# RANGKAIAN_SISTEM_KESELURUHAN.net
KiCad netlist of a schematic drawn in EasyEDA
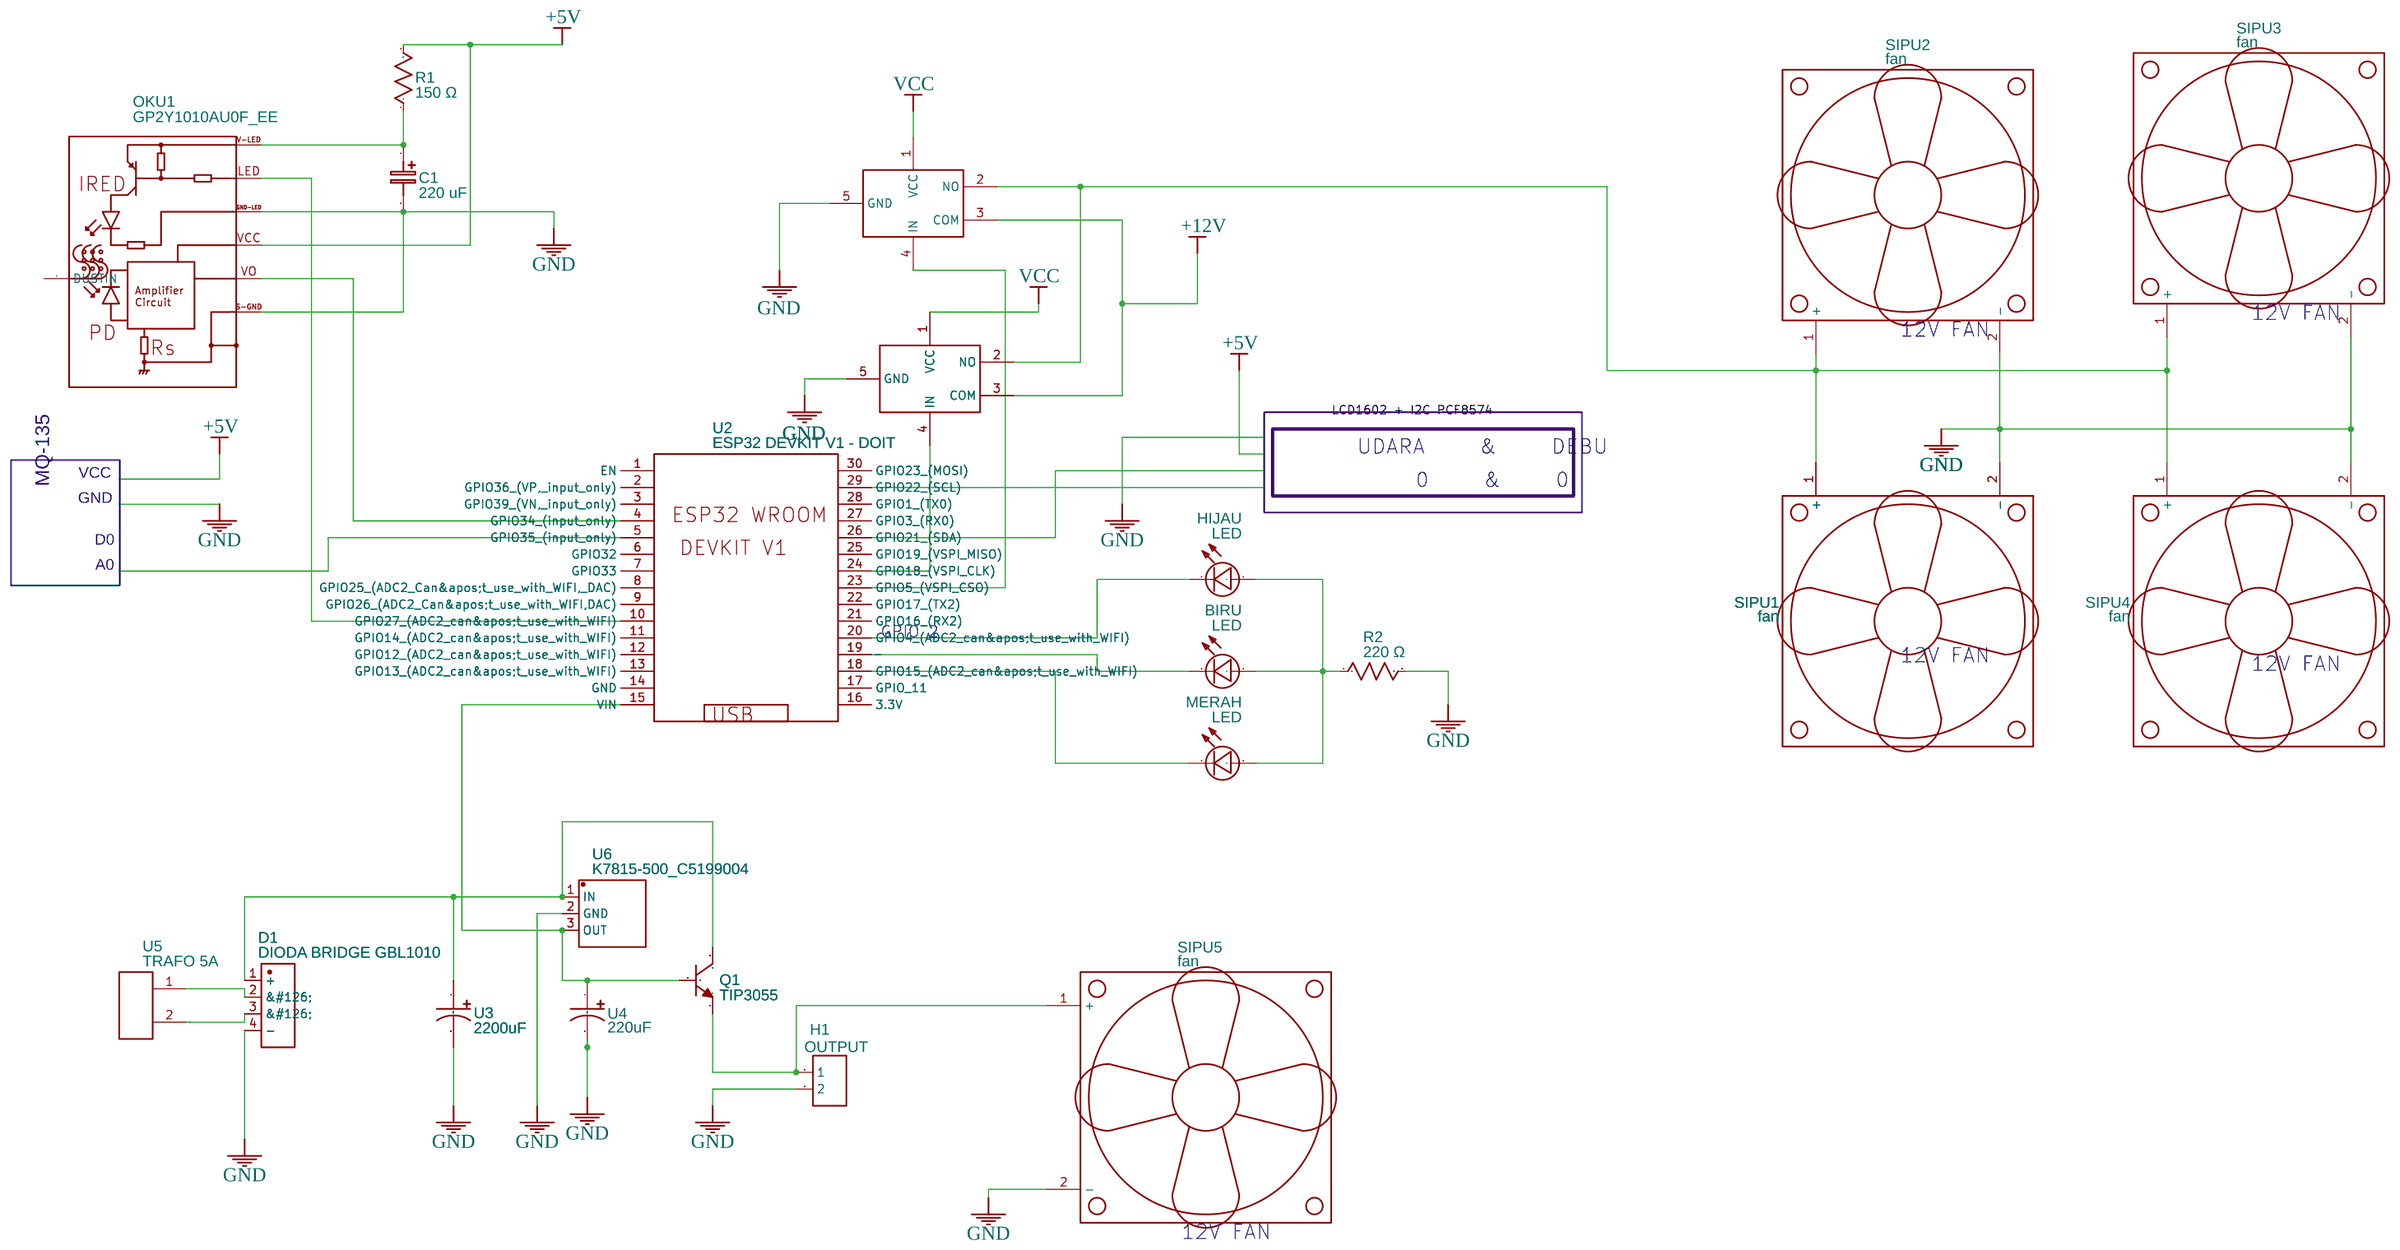
[diagram p0: schematic sheet]

(export (version "E")
  (design (tool "Eeschema 10.0.6"))
  (components
    (comp (ref "BIRU") (value "LED") (libsource (lib "") (part "LED_2")))
    (comp (ref "C1") (value "220 uF") (libsource (lib "") (part "C_Tan_SMD_A_EU")))
    (comp (ref "D1")
      (value "DIODA BRIDGE GBL1010")
      (fields (field (name "BOM_Manufacturer Part") "GBU1010") (field (name "BOM_Supplier Part") "C525760"))
      (libsource (lib "") (part "Dioda Bridge 10A"))
    )
    (comp (ref "H1")
      (value "OUTPUT")
      (fields (field (name "BOM_Supplier Part") "C49661"))
      (libsource (lib "") (part "HDR-F-2.54_1x2"))
    )
    (comp (ref "HIJAU") (value "LED") (libsource (lib "") (part "LED")))
    (comp (ref "MERAH") (value "LED") (libsource (lib "") (part "LED_1")))
    (comp (ref "OKU1")
      (value "GP2Y1010AU0F_EE")
      (fields (field (name "BOM_Manufacturer Part") "?"))
      (libsource (lib "") (part "GP2Y1010AU0F_EE_IN DEVELOPMENT"))
    )
    (comp (ref "Q1")
      (value "TIP3055")
      (fields
        (field (name "BOM_Manufacturer Part") "2n3904S-RTK/PS")
        (field (name "BOM_Supplier Part") "C18536")
      )
      (libsource (lib "") (part "2N3904(SOT-23)"))
    )
    (comp (ref "R1") (value "150 Ω") (libsource (lib "") (part "R_0603_US_1")))
    (comp (ref "R2") (value "220 Ω") (libsource (lib "") (part "R_0603_US")))
    (comp (ref "SIPU1")
      (value "fan")
      (fields (field (name "BOM_Manufacturer Part") "?"))
      (libsource (lib "") (part "Unknown_1165_-415"))
    )
    (comp (ref "SIPU2")
      (value "fan")
      (fields (field (name "BOM_Manufacturer Part") "?"))
      (libsource (lib "") (part "Unknown_1165_-660"))
    )
    (comp (ref "SIPU3")
      (value "fan")
      (fields (field (name "BOM_Manufacturer Part") "?"))
      (libsource (lib "") (part "Unknown_1375_-670"))
    )
    (comp (ref "SIPU4")
      (value "fan")
      (fields (field (name "BOM_Manufacturer Part") "?"))
      (libsource (lib "") (part "Unknown_1375_-415"))
    )
    (comp (ref "SIPU5")
      (value "fan")
      (fields (field (name "BOM_Manufacturer Part") "?"))
      (libsource (lib "") (part "Unknown_735_-120"))
    )
    (comp (ref "U1") (value "Relay 5P") (libsource (lib "") (part "Relay 5P")))
    (comp (ref "U2") (value "ESP32 DEVKIT V1 - DOIT") (libsource (lib "") (part "ESP32 DEVKIT V1 - DOIT")))
    (comp (ref "U3") (value "2200uF") (libsource (lib "") (part "kapasitor")))
    (comp (ref "U4") (value "220uF") (libsource (lib "") (part "kapasitor")))
    (comp (ref "U5") (value "TRAFO 5A") (libsource (lib "") (part "Kapasitor_yatik")))
    (comp (ref "U6")
      (value "K7815-500_C5199004")
      (fields
        (field (name "BOM_Manufacturer Part") "K7809-500")
        (field (name "BOM_Supplier Part") "C5199004")
      )
      (libsource (lib "") (part "K7809-500_C5199004"))
    )
    (comp (ref "U7") (value "Relay 5P") (libsource (lib "") (part "Relay 5P")))
  )
  (nets
    (net (code "1") (name "+5V") (class "Default")
      (node (ref "OKU1") (pin "VCC") (pinfunction "VCC_VCC") (pintype "input"))
      (node (ref "R1") (pin "2") (pinfunction "2_2") (pintype "unspecified"))
    )
    (net (code "2") (name "+12V") (class "Default")
      (node (ref "U1") (pin "3") (pinfunction "COM_3") (pintype "output"))
      (node (ref "U7") (pin "3") (pinfunction "COM_3") (pintype "output"))
    )
    (net (code "4") (name "GND") (class "Default")
      (node (ref "C1") (pin "2") (pinfunction "2_2") (pintype "unspecified"))
      (node (ref "D1") (pin "4") (pinfunction "-_4") (pintype "unspecified"))
      (node (ref "H1") (pin "2") (pinfunction "2_2") (pintype "input"))
      (node (ref "OKU1") (pin "GND-LED") (pinfunction "LEDGND_GND-LED") (pintype "input"))
      (node (ref "OKU1") (pin "S-GND") (pinfunction "SGND_S-GND") (pintype "input"))
      (node (ref "R2") (pin "2") (pinfunction "2_2") (pintype "unspecified"))
      (node (ref "SIPU1") (pin "2") (pinfunction "-_2") (pintype "unspecified"))
      (node (ref "SIPU2") (pin "2") (pinfunction "-_2") (pintype "unspecified"))
      (node (ref "SIPU3") (pin "2") (pinfunction "-_2") (pintype "unspecified"))
      (node (ref "SIPU4") (pin "2") (pinfunction "-_2") (pintype "unspecified"))
      (node (ref "SIPU5") (pin "2") (pinfunction "-_2") (pintype "unspecified"))
      (node (ref "U1") (pin "5") (pinfunction "GND_5") (pintype "input"))
      (node (ref "U3") (pin "2") (pinfunction "2_2") (pintype "unspecified"))
      (node (ref "U4") (pin "2") (pinfunction "2_2") (pintype "unspecified"))
      (node (ref "U6") (pin "2") (pinfunction "GND_2") (pintype "unspecified"))
      (node (ref "U7") (pin "5") (pinfunction "GND_5") (pintype "input"))
    )
    (net (code "5") (name "Net-(BIRU-+)") (class "Default")
      (node (ref "BIRU") (pin "1") (pinfunction "+_1") (pintype "unspecified"))
      (node (ref "HIJAU") (pin "1") (pinfunction "+_1") (pintype "unspecified"))
      (node (ref "MERAH") (pin "1") (pinfunction "+_1") (pintype "unspecified"))
      (node (ref "R2") (pin "1") (pinfunction "1_1") (pintype "unspecified"))
    )
    (net (code "6") (name "Net-(BIRU--)") (class "Default")
      (node (ref "BIRU") (pin "2") (pinfunction "-_2") (pintype "unspecified"))
      (node (ref "U2") (pin "19") (pinfunction "GPIO2_(ADC2_can&apos;t_use_with_WIFI)_19") (pintype "unspecified"))
    )
    (net (code "7") (name "Net-(D1-+)") (class "Default")
      (node (ref "D1") (pin "1") (pinfunction "+_1") (pintype "unspecified"))
      (node (ref "Q1") (pin "3") (pinfunction "C_3") (pintype "input"))
      (node (ref "U3") (pin "1") (pinfunction "1_1") (pintype "unspecified"))
      (node (ref "U6") (pin "1") (pinfunction "IN_1") (pintype "unspecified"))
    )
    (net (code "8") (name "Net-(HIJAU--)") (class "Default")
      (node (ref "HIJAU") (pin "2") (pinfunction "-_2") (pintype "unspecified"))
      (node (ref "U2") (pin "20") (pinfunction "GPIO4_(ADC2_can&apos;t_use_with_WIFI)_20") (pintype "unspecified"))
    )
    (net (code "9") (name "Net-(MERAH--)") (class "Default")
      (node (ref "MERAH") (pin "2") (pinfunction "-_2") (pintype "unspecified"))
      (node (ref "U2") (pin "18") (pinfunction "GPIO15_(ADC2_can&apos;t_use_with_WIFI)_18") (pintype "unspecified"))
    )
    (net (code "10") (name "Net-(OKU1-VLED)") (class "Default")
      (node (ref "C1") (pin "1") (pinfunction "1_1") (pintype "unspecified"))
      (node (ref "OKU1") (pin "V-LED") (pinfunction "VLED_V-LED") (pintype "input"))
      (node (ref "R1") (pin "1") (pinfunction "1_1") (pintype "unspecified"))
    )
    (net (code "11") (name "Net-(Q1-B)") (class "Default")
      (node (ref "Q1") (pin "2") (pinfunction "B_2") (pintype "input"))
      (node (ref "U2") (pin "15") (pinfunction "VIN_15") (pintype "unspecified"))
      (node (ref "U4") (pin "1") (pinfunction "1_1") (pintype "unspecified"))
      (node (ref "U6") (pin "3") (pinfunction "OUT_3") (pintype "unspecified"))
    )
    (net (code "12") (name "Net-(Q1-E)") (class "Default")
      (node (ref "H1") (pin "1") (pinfunction "1_1") (pintype "input"))
      (node (ref "Q1") (pin "1") (pinfunction "E_1") (pintype "input"))
      (node (ref "SIPU5") (pin "1") (pinfunction "+_1") (pintype "unspecified"))
    )
    (net (code "13") (name "Net-(SIPU1-+)") (class "Default")
      (node (ref "SIPU1") (pin "1") (pinfunction "+_1") (pintype "unspecified"))
      (node (ref "SIPU2") (pin "1") (pinfunction "+_1") (pintype "unspecified"))
      (node (ref "SIPU3") (pin "1") (pinfunction "+_1") (pintype "unspecified"))
      (node (ref "SIPU4") (pin "1") (pinfunction "+_1") (pintype "unspecified"))
      (node (ref "U1") (pin "2") (pinfunction "NO_2") (pintype "output"))
      (node (ref "U7") (pin "2") (pinfunction "NO_2") (pintype "output"))
    )
    (net (code "14") (name "Net-(U1-IN)") (class "Default")
      (node (ref "U1") (pin "4") (pinfunction "IN_4") (pintype "bidirectional"))
      (node (ref "U2") (pin "24") (pinfunction "GPIO18_(VSPI_CLK)_24") (pintype "unspecified"))
    )
    (net (code "15") (name "Net-(U2-GPIO5_(VSPI_CSO))") (class "Default")
      (node (ref "U2") (pin "23") (pinfunction "GPIO5_(VSPI_CSO)_23") (pintype "unspecified"))
      (node (ref "U7") (pin "4") (pinfunction "IN_4") (pintype "bidirectional"))
    )
    (net (code "16") (name "Net-(U2-GPIO27_(ADC2_can&apos;t_use_with_WIFI))") (class "Default")
      (node (ref "OKU1") (pin "LED") (pinfunction "LED_LED") (pintype "input"))
      (node (ref "U2") (pin "10") (pinfunction "GPIO27_(ADC2_can&apos;t_use_with_WIFI)_10") (pintype "unspecified"))
    )
    (net (code "17") (name "Net-(U2-GPIO34_(input_only))") (class "Default")
      (node (ref "OKU1") (pin "VO") (pinfunction "VO_VO") (pintype "input"))
      (node (ref "U2") (pin "4") (pinfunction "GPIO34_(input_only)_4") (pintype "unspecified"))
    )
    (net (code "18") (name "VCC") (class "Default")
      (node (ref "U1") (pin "1") (pinfunction "VCC_1") (pintype "bidirectional"))
      (node (ref "U7") (pin "1") (pinfunction "VCC_1") (pintype "bidirectional"))
    )
    (net (code "19") (name "unconnected-(D1-&#126;-Pad2)") (class "Default")
      (node (ref "D1") (pin "2") (pinfunction "&#126;_2") (pintype "unspecified"))
    )
    (net (code "20") (name "unconnected-(D1-&#126;-Pad3)") (class "Default")
      (node (ref "D1") (pin "3") (pinfunction "&#126;_3") (pintype "unspecified"))
    )
    (net (code "21") (name "unconnected-(OKU1-DUSTIN-Pad7)") (class "Default")
      (node (ref "OKU1") (pin "7") (pinfunction "DUSTIN_7") (pintype "unspecified"))
    )
    (net (code "22") (name "unconnected-(U2-3.3V-Pad16)") (class "Default")
      (node (ref "U2") (pin "16") (pinfunction "3.3V_16") (pintype "unspecified"))
    )
    (net (code "23") (name "unconnected-(U2-EN-Pad1)") (class "Default")
      (node (ref "U2") (pin "1") (pinfunction "EN_1") (pintype "unspecified"))
    )
    (net (code "24") (name "unconnected-(U2-GND-Pad14)") (class "Default")
      (node (ref "U2") (pin "14") (pinfunction "GND_14") (pintype "unspecified"))
    )
    (net (code "25") (name "unconnected-(U2-GPIO1_(TX0)-Pad28)") (class "Default")
      (node (ref "U2") (pin "28") (pinfunction "GPIO1_(TX0)_28") (pintype "unspecified"))
    )
    (net (code "26") (name "unconnected-(U2-GPIO3_(RX0)-Pad27)") (class "Default")
      (node (ref "U2") (pin "27") (pinfunction "GPIO3_(RX0)_27") (pintype "unspecified"))
    )
    (net (code "27") (name "unconnected-(U2-GPIO12_(ADC2_can&apos;t_use_with_WIFI)-Pad12)") (class "Default")
      (node (ref "U2") (pin "12") (pinfunction "GPIO12_(ADC2_can&apos;t_use_with_WIFI)_12") (pintype "unspecified"))
    )
    (net (code "28") (name "unconnected-(U2-GPIO13_(ADC2_can&apos;t_use_with_WIFI)-Pad13)") (class "Default")
      (node (ref "U2") (pin "13") (pinfunction "GPIO13_(ADC2_can&apos;t_use_with_WIFI)_13") (pintype "unspecified"))
    )
    (net (code "29") (name "unconnected-(U2-GPIO14_(ADC2_can&apos;t_use_with_WIFI)-Pad11)") (class "Default")
      (node (ref "U2") (pin "11") (pinfunction "GPIO14_(ADC2_can&apos;t_use_with_WIFI)_11") (pintype "unspecified"))
    )
    (net (code "30") (name "unconnected-(U2-GPIO16_(RX2)-Pad21)") (class "Default")
      (node (ref "U2") (pin "21") (pinfunction "GPIO16_(RX2)_21") (pintype "unspecified"))
    )
    (net (code "31") (name "unconnected-(U2-GPIO17_(TX2)-Pad22)") (class "Default")
      (node (ref "U2") (pin "22") (pinfunction "GPIO17_(TX2)_22") (pintype "unspecified"))
    )
    (net (code "32") (name "unconnected-(U2-GPIO19_(VSPI_MISO)-Pad25)") (class "Default")
      (node (ref "U2") (pin "25") (pinfunction "GPIO19_(VSPI_MISO)_25") (pintype "unspecified"))
    )
    (net (code "33") (name "unconnected-(U2-GPIO21_(SDA)-Pad26)") (class "Default")
      (node (ref "U2") (pin "26") (pinfunction "GPIO21_(SDA)_26") (pintype "unspecified"))
    )
    (net (code "34") (name "unconnected-(U2-GPIO22_(SCL)-Pad29)") (class "Default")
      (node (ref "U2") (pin "29") (pinfunction "GPIO22_(SCL)_29") (pintype "unspecified"))
    )
    (net (code "35") (name "unconnected-(U2-GPIO23_(MOSI)-Pad30)") (class "Default")
      (node (ref "U2") (pin "30") (pinfunction "GPIO23_(MOSI)_30") (pintype "unspecified"))
    )
    (net (code "36") (name "unconnected-(U2-GPIO25_(ADC2_Can&apos;t_use_with_WIFI,_DAC)-Pad8)") (class "Default")
      (node (ref "U2") (pin "8") (pinfunction "GPIO25_(ADC2_Can&apos;t_use_with_WIFI,_DAC)_8") (pintype "unspecified"))
    )
    (net (code "37") (name "unconnected-(U2-GPIO26_(ADC2_Can&apos;t_use_with_WIFI,DAC)-Pad9)") (class "Default")
      (node (ref "U2") (pin "9") (pinfunction "GPIO26_(ADC2_Can&apos;t_use_with_WIFI,DAC)_9") (pintype "unspecified"))
    )
    (net (code "38") (name "unconnected-(U2-GPIO32-Pad6)") (class "Default")
      (node (ref "U2") (pin "6") (pinfunction "GPIO32_6") (pintype "unspecified"))
    )
    (net (code "39") (name "unconnected-(U2-GPIO33-Pad7)") (class "Default")
      (node (ref "U2") (pin "7") (pinfunction "GPIO33_7") (pintype "unspecified"))
    )
    (net (code "40") (name "unconnected-(U2-GPIO35_(input_only)-Pad5)") (class "Default")
      (node (ref "U2") (pin "5") (pinfunction "GPIO35_(input_only)_5") (pintype "unspecified"))
    )
    (net (code "41") (name "unconnected-(U2-GPIO36_(VP,_input_only)-Pad2)") (class "Default")
      (node (ref "U2") (pin "2") (pinfunction "GPIO36_(VP,_input_only)_2") (pintype "unspecified"))
    )
    (net (code "42") (name "unconnected-(U2-GPIO39_(VN,_input_only)-Pad3)") (class "Default")
      (node (ref "U2") (pin "3") (pinfunction "GPIO39_(VN,_input_only)_3") (pintype "unspecified"))
    )
    (net (code "43") (name "unconnected-(U2-GPIO_11-Pad17)") (class "Default")
      (node (ref "U2") (pin "17") (pinfunction "GPIO_11_17") (pintype "unspecified"))
    )
    (net (code "44") (name "unconnected-(U5-+-Pad2)") (class "Default")
      (node (ref "U5") (pin "2") (pinfunction "+_2") (pintype "unspecified"))
    )
    (net (code "45") (name "unconnected-(U5---Pad1)") (class "Default")
      (node (ref "U5") (pin "1") (pinfunction "-_1") (pintype "unspecified"))
    )
  )
)
